# 16n.net
KiCad netlist of a schematic drawn in EAGLE
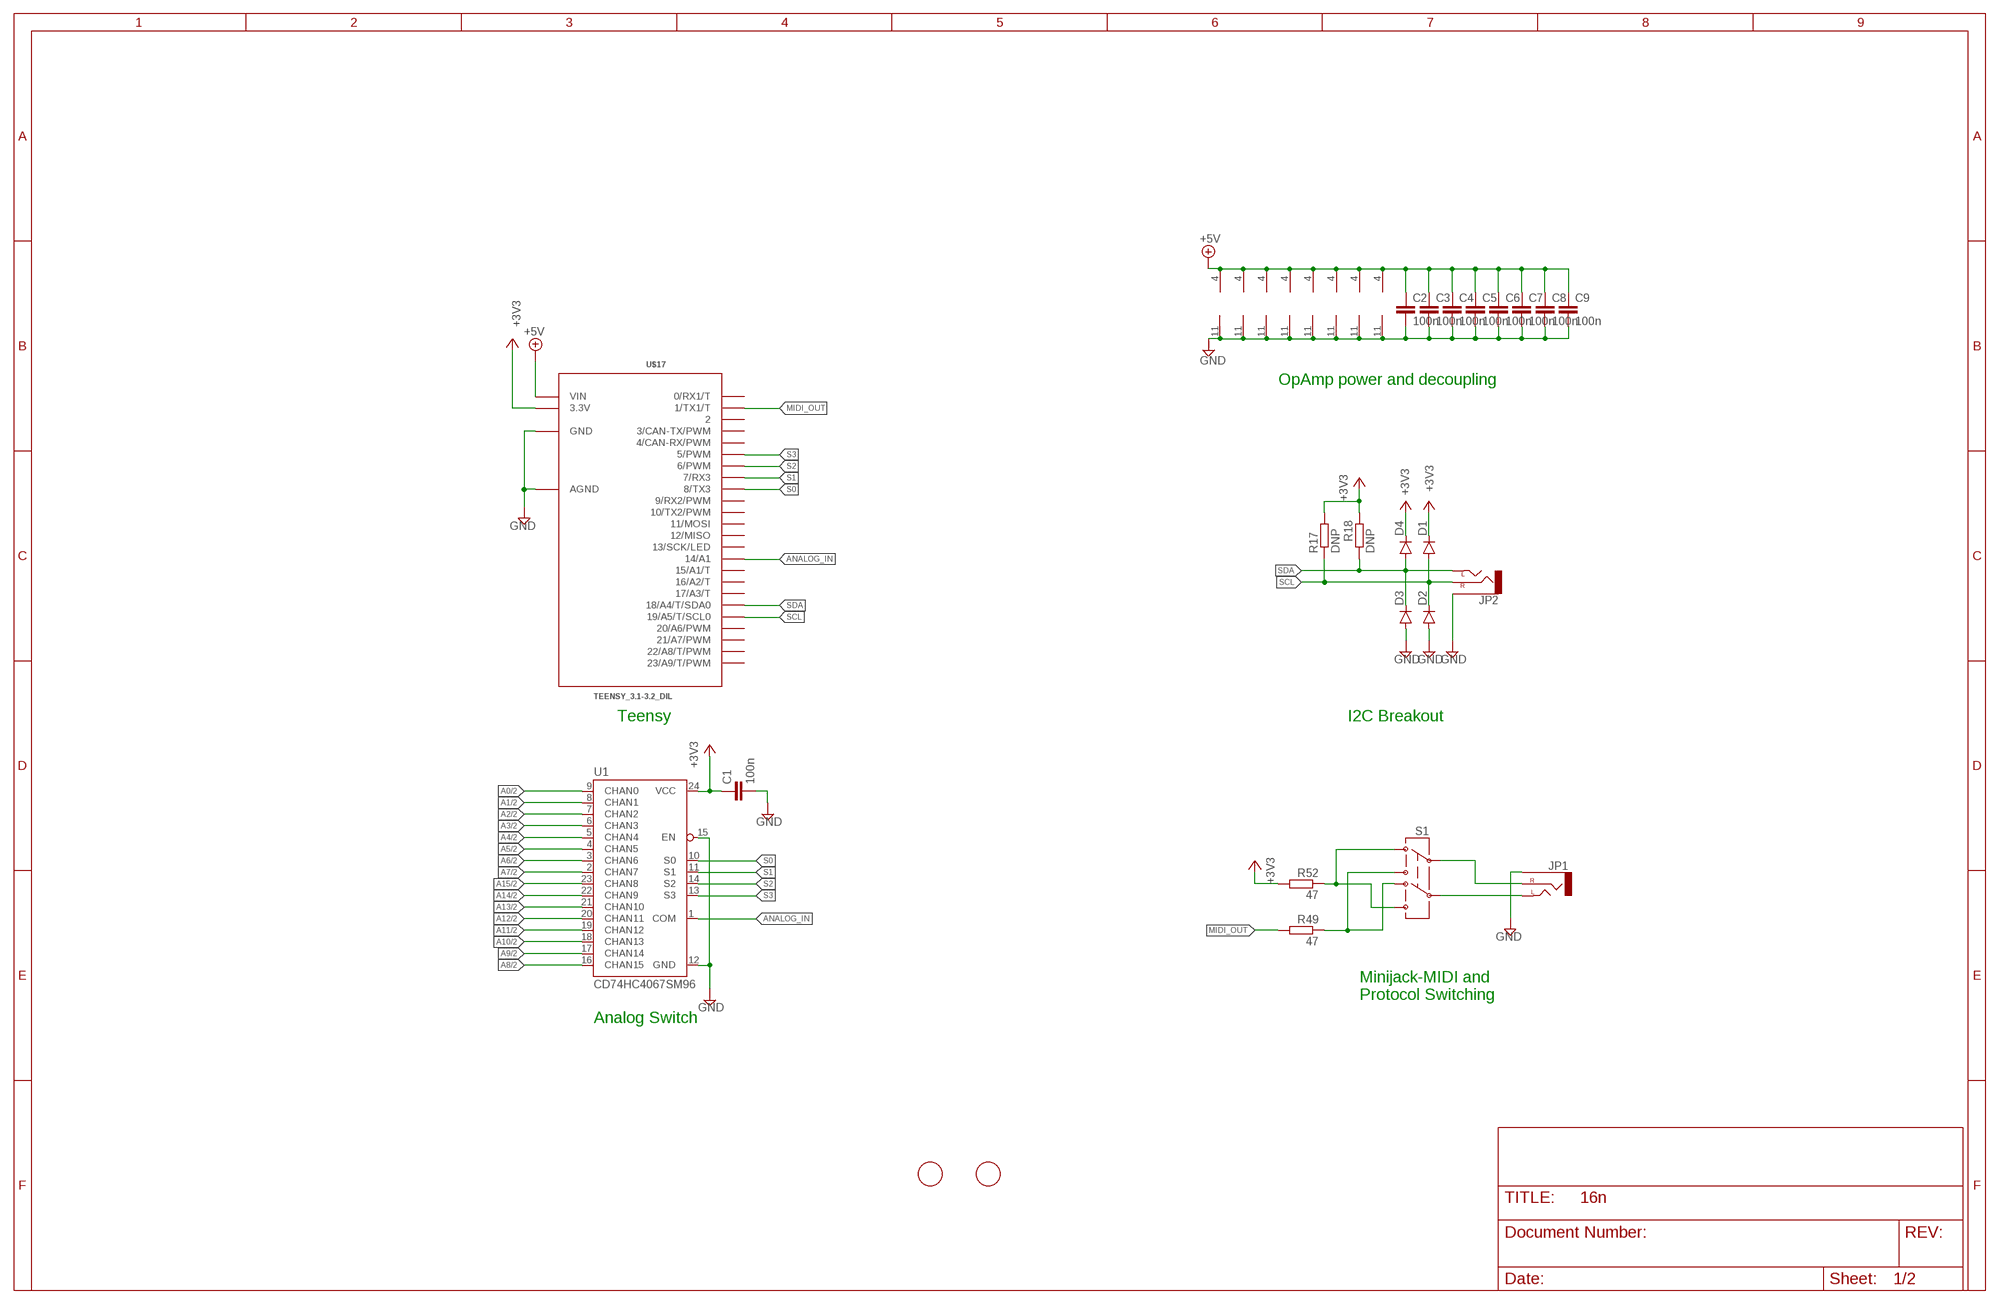
[diagram p0: schematic, sheet 1]
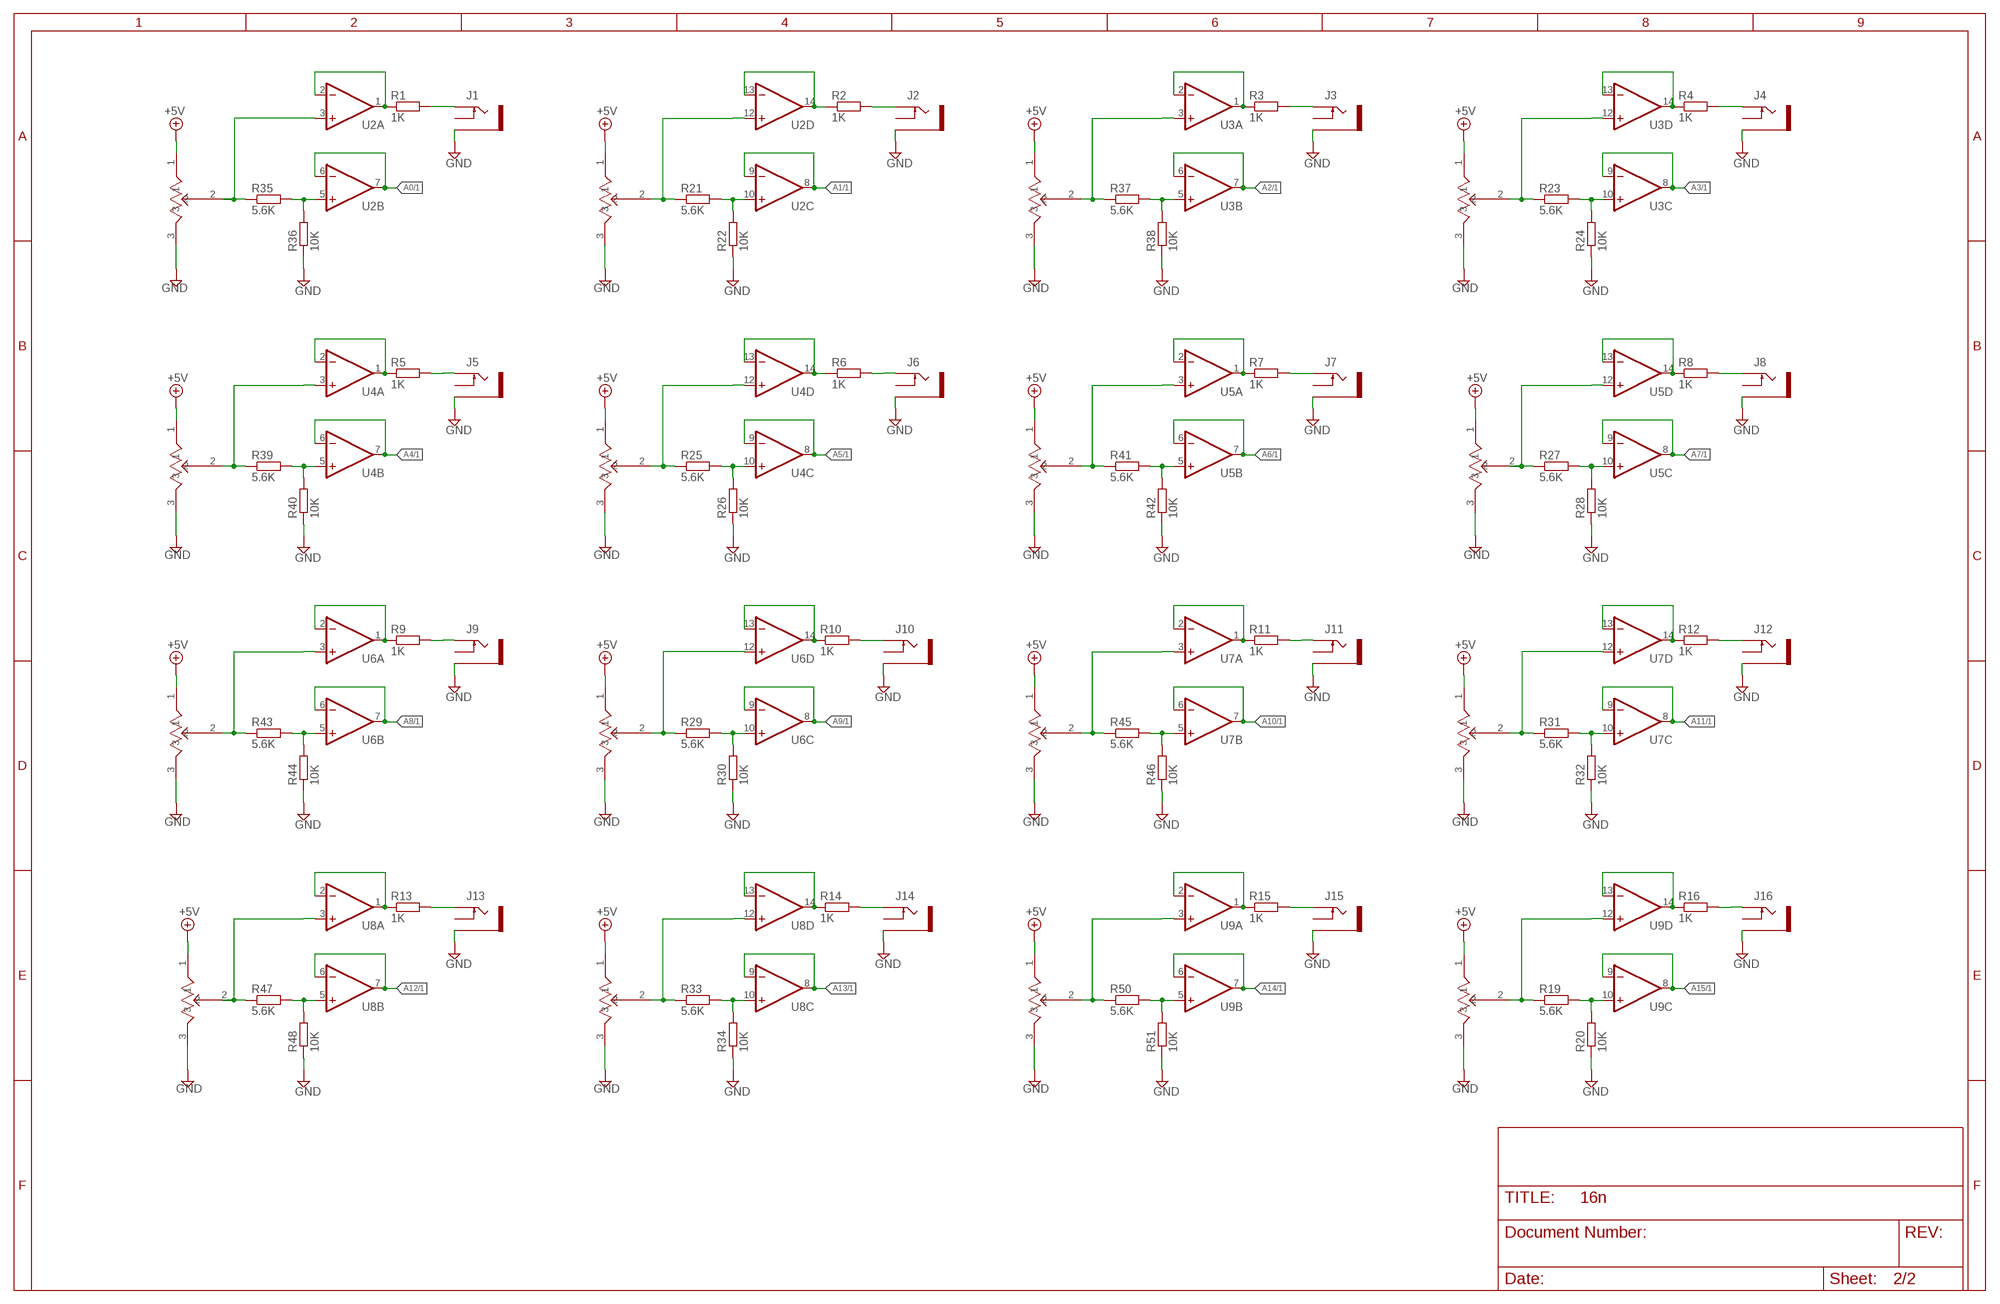
[diagram p1: schematic, sheet 2]

(export (version "E")
  (design (tool "Eeschema 10.0.6"))
  (components
    (comp (ref "C1")
      (value "100n")
      (footprint "eagle-import:C0805")
      (libsource (lib "eagle-import") (part "C-EUC0805"))
    )
    (comp (ref "C2")
      (value "100n")
      (footprint "eagle-import:C0805")
      (libsource (lib "eagle-import") (part "C-EUC0805"))
    )
    (comp (ref "C3")
      (value "100n")
      (footprint "eagle-import:C0805")
      (libsource (lib "eagle-import") (part "C-EUC0805"))
    )
    (comp (ref "C4")
      (value "100n")
      (footprint "eagle-import:C0805")
      (libsource (lib "eagle-import") (part "C-EUC0805"))
    )
    (comp (ref "C5")
      (value "100n")
      (footprint "eagle-import:C0805")
      (libsource (lib "eagle-import") (part "C-EUC0805"))
    )
    (comp (ref "C6")
      (value "100n")
      (footprint "eagle-import:C0805")
      (libsource (lib "eagle-import") (part "C-EUC0805"))
    )
    (comp (ref "C7")
      (value "100n")
      (footprint "eagle-import:C0805")
      (libsource (lib "eagle-import") (part "C-EUC0805"))
    )
    (comp (ref "C8")
      (value "100n")
      (footprint "eagle-import:C0805")
      (libsource (lib "eagle-import") (part "C-EUC0805"))
    )
    (comp (ref "C9")
      (value "100n")
      (footprint "eagle-import:C0805")
      (libsource (lib "eagle-import") (part "C-EUC0805"))
    )
    (comp (ref "D1")
      (value "DIODESOD123")
      (footprint "eagle-import:SOD-123")
      (libsource (lib "eagle-import") (part "DIODESOD123"))
    )
    (comp (ref "D2")
      (value "DIODESOD123")
      (footprint "eagle-import:SOD-123")
      (libsource (lib "eagle-import") (part "DIODESOD123"))
    )
    (comp (ref "D3")
      (value "DIODESOD123")
      (footprint "eagle-import:SOD-123")
      (libsource (lib "eagle-import") (part "DIODESOD123"))
    )
    (comp (ref "D4")
      (value "DIODESOD123")
      (footprint "eagle-import:SOD-123")
      (libsource (lib "eagle-import") (part "DIODESOD123"))
    )
    (comp (ref "FID1")
      (value "FIDUCIAL")
      (footprint "eagle-import:FIDUCIAL_1MM")
      (libsource (lib "eagle-import") (part "FIDUCIAL"))
    )
    (comp (ref "FID2")
      (value "FIDUCIAL")
      (footprint "eagle-import:FIDUCIAL_1MM")
      (libsource (lib "eagle-import") (part "FIDUCIAL"))
    )
    (comp (ref "JP1")
      (value "AUDIO-JACKPTH")
      (footprint "eagle-import:AUDIO-JACK")
      (libsource (lib "eagle-import") (part "AUDIO-JACKPTH"))
    )
    (comp (ref "JP2")
      (value "AUDIO-JACKPTH")
      (footprint "eagle-import:AUDIO-JACK")
      (libsource (lib "eagle-import") (part "AUDIO-JACKPTH"))
    )
    (comp (ref "R17")
      (value "DNP")
      (footprint "eagle-import:R0805")
      (libsource (lib "eagle-import") (part "R-EU_R0805"))
    )
    (comp (ref "R18")
      (value "DNP")
      (footprint "eagle-import:R0805")
      (libsource (lib "eagle-import") (part "R-EU_R0805"))
    )
    (comp (ref "R49")
      (value "47")
      (footprint "eagle-import:R0805")
      (libsource (lib "eagle-import") (part "R-EU_R0805"))
    )
    (comp (ref "R52")
      (value "47")
      (footprint "eagle-import:R0805")
      (libsource (lib "eagle-import") (part "R-EU_R0805"))
    )
    (comp (ref "S1")
      (value "SWITCH-DPDTEG2211")
      (footprint "eagle-import:EG2211")
      (libsource (lib "eagle-import") (part "SWITCH-DPDTEG2211"))
    )
    (comp (ref "U$17")
      (value "TEENSY_3.1-3.2_DIL")
      (footprint "eagle-import:TEENSY_3.0-3.2&LC_DIL")
      (libsource (lib "eagle-import") (part "TEENSY_3.1-3.2_DIL"))
    )
    (comp (ref "U1")
      (value "CD74HC4067SM96")
      (footprint "eagle-import:SOIC127P1030X265-24")
      (libsource (lib "eagle-import") (part "744067SO24"))
    )
    (comp (ref "U2")
      (value "MCP6004_SMD")
      (footprint "eagle-import:SO14")
      (libsource (lib "eagle-import") (part "MCP6004_SMD"))
    )
    (comp (ref "U3")
      (value "MCP6004_SMD")
      (footprint "eagle-import:SO14")
      (libsource (lib "eagle-import") (part "MCP6004_SMD"))
    )
    (comp (ref "U4")
      (value "MCP6004_SMD")
      (footprint "eagle-import:SO14")
      (libsource (lib "eagle-import") (part "MCP6004_SMD"))
    )
    (comp (ref "U5")
      (value "MCP6004_SMD")
      (footprint "eagle-import:SO14")
      (libsource (lib "eagle-import") (part "MCP6004_SMD"))
    )
    (comp (ref "U6")
      (value "MCP6004_SMD")
      (footprint "eagle-import:SO14")
      (libsource (lib "eagle-import") (part "MCP6004_SMD"))
    )
    (comp (ref "U7")
      (value "MCP6004_SMD")
      (footprint "eagle-import:SO14")
      (libsource (lib "eagle-import") (part "MCP6004_SMD"))
    )
    (comp (ref "U8")
      (value "MCP6004_SMD")
      (footprint "eagle-import:SO14")
      (libsource (lib "eagle-import") (part "MCP6004_SMD"))
    )
    (comp (ref "U9")
      (value "MCP6004")
      (footprint "eagle-import:SO14")
      (libsource (lib "eagle-import") (part "MCP6004_SMD"))
    )
    (comp (ref "J1")
      (value "PJ302M")
      (footprint "eagle-import:PJ302M")
      (libsource (lib "eagle-import") (part "PJ302M"))
    )
    (comp (ref "J2")
      (value "PJ302M")
      (footprint "eagle-import:PJ302M")
      (libsource (lib "eagle-import") (part "PJ302M"))
    )
    (comp (ref "J3")
      (value "PJ302M")
      (footprint "eagle-import:PJ302M")
      (libsource (lib "eagle-import") (part "PJ302M"))
    )
    (comp (ref "J4")
      (value "PJ302M")
      (footprint "eagle-import:PJ302M")
      (libsource (lib "eagle-import") (part "PJ302M"))
    )
    (comp (ref "J5")
      (value "PJ302M")
      (footprint "eagle-import:PJ302M")
      (libsource (lib "eagle-import") (part "PJ302M"))
    )
    (comp (ref "J6")
      (value "PJ302M")
      (footprint "eagle-import:PJ302M")
      (libsource (lib "eagle-import") (part "PJ302M"))
    )
    (comp (ref "J7")
      (value "PJ302M")
      (footprint "eagle-import:PJ302M")
      (libsource (lib "eagle-import") (part "PJ302M"))
    )
    (comp (ref "J8")
      (value "PJ302M")
      (footprint "eagle-import:PJ302M")
      (libsource (lib "eagle-import") (part "PJ302M"))
    )
    (comp (ref "J9")
      (value "PJ302M")
      (footprint "eagle-import:PJ302M")
      (libsource (lib "eagle-import") (part "PJ302M"))
    )
    (comp (ref "J10")
      (value "PJ302M")
      (footprint "eagle-import:PJ302M")
      (libsource (lib "eagle-import") (part "PJ302M"))
    )
    (comp (ref "J11")
      (value "PJ302M")
      (footprint "eagle-import:PJ302M")
      (libsource (lib "eagle-import") (part "PJ302M"))
    )
    (comp (ref "J12")
      (value "PJ302M")
      (footprint "eagle-import:PJ302M")
      (libsource (lib "eagle-import") (part "PJ302M"))
    )
    (comp (ref "J13")
      (value "PJ302M")
      (footprint "eagle-import:PJ302M")
      (libsource (lib "eagle-import") (part "PJ302M"))
    )
    (comp (ref "J14")
      (value "PJ302M")
      (footprint "eagle-import:PJ302M")
      (libsource (lib "eagle-import") (part "PJ302M"))
    )
    (comp (ref "J15")
      (value "PJ302M")
      (footprint "eagle-import:PJ302M")
      (libsource (lib "eagle-import") (part "PJ302M"))
    )
    (comp (ref "J16")
      (value "PJ302M")
      (footprint "eagle-import:PJ302M")
      (libsource (lib "eagle-import") (part "PJ302M"))
    )
    (comp (ref "R1")
      (value "1K")
      (footprint "eagle-import:R0805")
      (libsource (lib "eagle-import") (part "R-EU_R0805"))
    )
    (comp (ref "R2")
      (value "1K")
      (footprint "eagle-import:R0805")
      (libsource (lib "eagle-import") (part "R-EU_R0805"))
    )
    (comp (ref "R3")
      (value "1K")
      (footprint "eagle-import:R0805")
      (libsource (lib "eagle-import") (part "R-EU_R0805"))
    )
    (comp (ref "R4")
      (value "1K")
      (footprint "eagle-import:R0805")
      (libsource (lib "eagle-import") (part "R-EU_R0805"))
    )
    (comp (ref "R5")
      (value "1K")
      (footprint "eagle-import:R0805")
      (libsource (lib "eagle-import") (part "R-EU_R0805"))
    )
    (comp (ref "R6")
      (value "1K")
      (footprint "eagle-import:R0805")
      (libsource (lib "eagle-import") (part "R-EU_R0805"))
    )
    (comp (ref "R7")
      (value "1K")
      (footprint "eagle-import:R0805")
      (libsource (lib "eagle-import") (part "R-EU_R0805"))
    )
    (comp (ref "R8")
      (value "1K")
      (footprint "eagle-import:R0805")
      (libsource (lib "eagle-import") (part "R-EU_R0805"))
    )
    (comp (ref "R9")
      (value "1K")
      (footprint "eagle-import:R0805")
      (libsource (lib "eagle-import") (part "R-EU_R0805"))
    )
    (comp (ref "R10")
      (value "1K")
      (footprint "eagle-import:R0805")
      (libsource (lib "eagle-import") (part "R-EU_R0805"))
    )
    (comp (ref "R11")
      (value "1K")
      (footprint "eagle-import:R0805")
      (libsource (lib "eagle-import") (part "R-EU_R0805"))
    )
    (comp (ref "R12")
      (value "1K")
      (footprint "eagle-import:R0805")
      (libsource (lib "eagle-import") (part "R-EU_R0805"))
    )
    (comp (ref "R13")
      (value "1K")
      (footprint "eagle-import:R0805")
      (libsource (lib "eagle-import") (part "R-EU_R0805"))
    )
    (comp (ref "R14")
      (value "1K")
      (footprint "eagle-import:R0805")
      (libsource (lib "eagle-import") (part "R-EU_R0805"))
    )
    (comp (ref "R15")
      (value "1K")
      (footprint "eagle-import:R0805")
      (libsource (lib "eagle-import") (part "R-EU_R0805"))
    )
    (comp (ref "R16")
      (value "1K")
      (footprint "eagle-import:R0805")
      (libsource (lib "eagle-import") (part "R-EU_R0805"))
    )
    (comp (ref "R19")
      (value "5.6K")
      (footprint "eagle-import:R0805")
      (libsource (lib "eagle-import") (part "R-EU_R0805"))
    )
    (comp (ref "R20")
      (value "10K")
      (footprint "eagle-import:R0805")
      (libsource (lib "eagle-import") (part "R-EU_R0805"))
    )
    (comp (ref "R21")
      (value "5.6K")
      (footprint "eagle-import:R0805")
      (libsource (lib "eagle-import") (part "R-EU_R0805"))
    )
    (comp (ref "R22")
      (value "10K")
      (footprint "eagle-import:R0805")
      (libsource (lib "eagle-import") (part "R-EU_R0805"))
    )
    (comp (ref "R23")
      (value "5.6K")
      (footprint "eagle-import:R0805")
      (libsource (lib "eagle-import") (part "R-EU_R0805"))
    )
    (comp (ref "R24")
      (value "10K")
      (footprint "eagle-import:R0805")
      (libsource (lib "eagle-import") (part "R-EU_R0805"))
    )
    (comp (ref "R25")
      (value "5.6K")
      (footprint "eagle-import:R0805")
      (libsource (lib "eagle-import") (part "R-EU_R0805"))
    )
    (comp (ref "R26")
      (value "10K")
      (footprint "eagle-import:R0805")
      (libsource (lib "eagle-import") (part "R-EU_R0805"))
    )
    (comp (ref "R27")
      (value "5.6K")
      (footprint "eagle-import:R0805")
      (libsource (lib "eagle-import") (part "R-EU_R0805"))
    )
    (comp (ref "R28")
      (value "10K")
      (footprint "eagle-import:R0805")
      (libsource (lib "eagle-import") (part "R-EU_R0805"))
    )
    (comp (ref "R29")
      (value "5.6K")
      (footprint "eagle-import:R0805")
      (libsource (lib "eagle-import") (part "R-EU_R0805"))
    )
    (comp (ref "R30")
      (value "10K")
      (footprint "eagle-import:R0805")
      (libsource (lib "eagle-import") (part "R-EU_R0805"))
    )
    (comp (ref "R31")
      (value "5.6K")
      (footprint "eagle-import:R0805")
      (libsource (lib "eagle-import") (part "R-EU_R0805"))
    )
    (comp (ref "R32")
      (value "10K")
      (footprint "eagle-import:R0805")
      (libsource (lib "eagle-import") (part "R-EU_R0805"))
    )
    (comp (ref "R33")
      (value "5.6K")
      (footprint "eagle-import:R0805")
      (libsource (lib "eagle-import") (part "R-EU_R0805"))
    )
    (comp (ref "R34")
      (value "10K")
      (footprint "eagle-import:R0805")
      (libsource (lib "eagle-import") (part "R-EU_R0805"))
    )
    (comp (ref "R35")
      (value "5.6K")
      (footprint "eagle-import:R0805")
      (libsource (lib "eagle-import") (part "R-EU_R0805"))
    )
    (comp (ref "R36")
      (value "10K")
      (footprint "eagle-import:R0805")
      (libsource (lib "eagle-import") (part "R-EU_R0805"))
    )
    (comp (ref "R37")
      (value "5.6K")
      (footprint "eagle-import:R0805")
      (libsource (lib "eagle-import") (part "R-EU_R0805"))
    )
    (comp (ref "R38")
      (value "10K")
      (footprint "eagle-import:R0805")
      (libsource (lib "eagle-import") (part "R-EU_R0805"))
    )
    (comp (ref "R39")
      (value "5.6K")
      (footprint "eagle-import:R0805")
      (libsource (lib "eagle-import") (part "R-EU_R0805"))
    )
    (comp (ref "R40")
      (value "10K")
      (footprint "eagle-import:R0805")
      (libsource (lib "eagle-import") (part "R-EU_R0805"))
    )
    (comp (ref "R41")
      (value "5.6K")
      (footprint "eagle-import:R0805")
      (libsource (lib "eagle-import") (part "R-EU_R0805"))
    )
    (comp (ref "R42")
      (value "10K")
      (footprint "eagle-import:R0805")
      (libsource (lib "eagle-import") (part "R-EU_R0805"))
    )
    (comp (ref "R43")
      (value "5.6K")
      (footprint "eagle-import:R0805")
      (libsource (lib "eagle-import") (part "R-EU_R0805"))
    )
    (comp (ref "R44")
      (value "10K")
      (footprint "eagle-import:R0805")
      (libsource (lib "eagle-import") (part "R-EU_R0805"))
    )
    (comp (ref "R45")
      (value "5.6K")
      (footprint "eagle-import:R0805")
      (libsource (lib "eagle-import") (part "R-EU_R0805"))
    )
    (comp (ref "R46")
      (value "10K")
      (footprint "eagle-import:R0805")
      (libsource (lib "eagle-import") (part "R-EU_R0805"))
    )
    (comp (ref "R47")
      (value "5.6K")
      (footprint "eagle-import:R0805")
      (libsource (lib "eagle-import") (part "R-EU_R0805"))
    )
    (comp (ref "R48")
      (value "10K")
      (footprint "eagle-import:R0805")
      (libsource (lib "eagle-import") (part "R-EU_R0805"))
    )
    (comp (ref "R50")
      (value "5.6K")
      (footprint "eagle-import:R0805")
      (libsource (lib "eagle-import") (part "R-EU_R0805"))
    )
    (comp (ref "R51")
      (value "10K")
      (footprint "eagle-import:R0805")
      (libsource (lib "eagle-import") (part "R-EU_R0805"))
    )
    (comp (ref "U$1")
      (value "SLIDEPOT-ALPS-60MM")
      (footprint "eagle-import:RS6011SP600")
      (libsource (lib "eagle-import") (part "SLIDEPOT-ALPS-60MM"))
    )
    (comp (ref "U$2")
      (value "SLIDEPOT-ALPS-60MM")
      (footprint "eagle-import:RS6011SP600")
      (libsource (lib "eagle-import") (part "SLIDEPOT-ALPS-60MM"))
    )
    (comp (ref "U$3")
      (value "SLIDEPOT-ALPS-60MM")
      (footprint "eagle-import:RS6011SP600")
      (libsource (lib "eagle-import") (part "SLIDEPOT-ALPS-60MM"))
    )
    (comp (ref "U$4")
      (value "SLIDEPOT-ALPS-60MM")
      (footprint "eagle-import:RS6011SP600")
      (libsource (lib "eagle-import") (part "SLIDEPOT-ALPS-60MM"))
    )
    (comp (ref "U$5")
      (value "SLIDEPOT-ALPS-60MM")
      (footprint "eagle-import:RS6011SP600")
      (libsource (lib "eagle-import") (part "SLIDEPOT-ALPS-60MM"))
    )
    (comp (ref "U$6")
      (value "SLIDEPOT-ALPS-60MM")
      (footprint "eagle-import:RS6011SP600")
      (libsource (lib "eagle-import") (part "SLIDEPOT-ALPS-60MM"))
    )
    (comp (ref "U$7")
      (value "SLIDEPOT-ALPS-60MM")
      (footprint "eagle-import:RS6011SP600")
      (libsource (lib "eagle-import") (part "SLIDEPOT-ALPS-60MM"))
    )
    (comp (ref "U$8")
      (value "SLIDEPOT-ALPS-60MM")
      (footprint "eagle-import:RS6011SP600")
      (libsource (lib "eagle-import") (part "SLIDEPOT-ALPS-60MM"))
    )
    (comp (ref "U$9")
      (value "SLIDEPOT-ALPS-60MM")
      (footprint "eagle-import:RS6011SP600")
      (libsource (lib "eagle-import") (part "SLIDEPOT-ALPS-60MM"))
    )
    (comp (ref "U$10")
      (value "SLIDEPOT-ALPS-60MM")
      (footprint "eagle-import:RS6011SP600")
      (fields (field (name "SPICEPREFIX") "U"))
      (libsource (lib "eagle-import") (part "SLIDEPOT-ALPS-60MM"))
    )
    (comp (ref "U$11")
      (value "SLIDEPOT-ALPS-60MM")
      (footprint "eagle-import:RS6011SP600")
      (libsource (lib "eagle-import") (part "SLIDEPOT-ALPS-60MM"))
    )
    (comp (ref "U$12")
      (value "SLIDEPOT-ALPS-60MM")
      (footprint "eagle-import:RS6011SP600")
      (libsource (lib "eagle-import") (part "SLIDEPOT-ALPS-60MM"))
    )
    (comp (ref "U$13")
      (value "SLIDEPOT-ALPS-60MM")
      (footprint "eagle-import:RS6011SP600")
      (libsource (lib "eagle-import") (part "SLIDEPOT-ALPS-60MM"))
    )
    (comp (ref "U$14")
      (value "SLIDEPOT-ALPS-60MM")
      (footprint "eagle-import:RS6011SP600")
      (libsource (lib "eagle-import") (part "SLIDEPOT-ALPS-60MM"))
    )
    (comp (ref "U$15")
      (value "SLIDEPOT-ALPS-60MM")
      (footprint "eagle-import:RS6011SP600")
      (libsource (lib "eagle-import") (part "SLIDEPOT-ALPS-60MM"))
    )
    (comp (ref "U$16")
      (value "SLIDEPOT-ALPS-60MM")
      (footprint "eagle-import:RS6011SP600")
      (libsource (lib "eagle-import") (part "SLIDEPOT-ALPS-60MM"))
    )
  )
  (nets
    (net (code "1") (name "+3V3") (class "Default")
      (node (ref "C1") (pin "1") (pinfunction "1_1") (pintype "passive"))
      (node (ref "D1") (pin "C") (pinfunction "C_C") (pintype "passive"))
      (node (ref "D4") (pin "C") (pinfunction "C_C") (pintype "passive"))
      (node (ref "R17") (pin "2") (pinfunction "2_2") (pintype "passive"))
      (node (ref "R18") (pin "2") (pinfunction "2_2") (pintype "passive"))
      (node (ref "R52") (pin "2") (pinfunction "2_2") (pintype "passive"))
      (node (ref "U$17") (pin "3.3V") (pinfunction "3.3V_3.3V") (pintype "power_in"))
      (node (ref "U1") (pin "24") (pinfunction "VCC_24") (pintype "bidirectional"))
    )
    (net (code "2") (name "+5V") (class "Default")
      (node (ref "C2") (pin "1") (pinfunction "1_1") (pintype "passive"))
      (node (ref "C3") (pin "1") (pinfunction "1_1") (pintype "passive"))
      (node (ref "C4") (pin "1") (pinfunction "1_1") (pintype "passive"))
      (node (ref "C5") (pin "1") (pinfunction "1_1") (pintype "passive"))
      (node (ref "C6") (pin "1") (pinfunction "1_1") (pintype "passive"))
      (node (ref "C7") (pin "1") (pinfunction "1_1") (pintype "passive"))
      (node (ref "C8") (pin "1") (pinfunction "1_1") (pintype "passive"))
      (node (ref "C9") (pin "1") (pinfunction "1_1") (pintype "passive"))
      (node (ref "U$1") (pin "1") (pinfunction "1_1") (pintype "bidirectional"))
      (node (ref "U$10") (pin "1") (pinfunction "1_1") (pintype "bidirectional"))
      (node (ref "U$11") (pin "1") (pinfunction "1_1") (pintype "bidirectional"))
      (node (ref "U$12") (pin "1") (pinfunction "1_1") (pintype "bidirectional"))
      (node (ref "U$13") (pin "1") (pinfunction "1_1") (pintype "bidirectional"))
      (node (ref "U$14") (pin "1") (pinfunction "1_1") (pintype "bidirectional"))
      (node (ref "U$15") (pin "1") (pinfunction "1_1") (pintype "bidirectional"))
      (node (ref "U$16") (pin "1") (pinfunction "1_1") (pintype "bidirectional"))
      (node (ref "U$17") (pin "VIN") (pinfunction "VIN_VIN") (pintype "power_in"))
      (node (ref "U$2") (pin "1") (pinfunction "1_1") (pintype "bidirectional"))
      (node (ref "U$3") (pin "1") (pinfunction "1_1") (pintype "bidirectional"))
      (node (ref "U$4") (pin "1") (pinfunction "1_1") (pintype "bidirectional"))
      (node (ref "U$5") (pin "1") (pinfunction "1_1") (pintype "bidirectional"))
      (node (ref "U$6") (pin "1") (pinfunction "1_1") (pintype "bidirectional"))
      (node (ref "U$7") (pin "1") (pinfunction "1_1") (pintype "bidirectional"))
      (node (ref "U$8") (pin "1") (pinfunction "1_1") (pintype "bidirectional"))
      (node (ref "U$9") (pin "1") (pinfunction "1_1") (pintype "bidirectional"))
      (node (ref "U2") (pin "4") (pinfunction "V+_4") (pintype "power_in"))
      (node (ref "U3") (pin "4") (pinfunction "V+_4") (pintype "power_in"))
      (node (ref "U4") (pin "4") (pinfunction "V+_4") (pintype "power_in"))
      (node (ref "U5") (pin "4") (pinfunction "V+_4") (pintype "power_in"))
      (node (ref "U6") (pin "4") (pinfunction "V+_4") (pintype "power_in"))
      (node (ref "U7") (pin "4") (pinfunction "V+_4") (pintype "power_in"))
      (node (ref "U8") (pin "4") (pinfunction "V+_4") (pintype "power_in"))
      (node (ref "U9") (pin "4") (pinfunction "V+_4") (pintype "power_in"))
    )
    (net (code "3") (name "A0") (class "Default")
      (node (ref "U1") (pin "9") (pinfunction "CHAN0_9") (pintype "bidirectional"))
      (node (ref "U2") (pin "6") (pinfunction "-IN_6") (pintype "input"))
      (node (ref "U2") (pin "7") (pinfunction "OUT_7") (pintype "output"))
    )
    (net (code "4") (name "A1") (class "Default")
      (node (ref "U1") (pin "8") (pinfunction "CHAN1_8") (pintype "bidirectional"))
      (node (ref "U2") (pin "8") (pinfunction "OUT_8") (pintype "output"))
      (node (ref "U2") (pin "9") (pinfunction "-IN_9") (pintype "input"))
    )
    (net (code "5") (name "A2") (class "Default")
      (node (ref "U1") (pin "7") (pinfunction "CHAN2_7") (pintype "bidirectional"))
      (node (ref "U3") (pin "6") (pinfunction "-IN_6") (pintype "input"))
      (node (ref "U3") (pin "7") (pinfunction "OUT_7") (pintype "output"))
    )
    (net (code "6") (name "A3") (class "Default")
      (node (ref "U1") (pin "6") (pinfunction "CHAN3_6") (pintype "bidirectional"))
      (node (ref "U3") (pin "8") (pinfunction "OUT_8") (pintype "output"))
      (node (ref "U3") (pin "9") (pinfunction "-IN_9") (pintype "input"))
    )
    (net (code "7") (name "A4") (class "Default")
      (node (ref "U1") (pin "5") (pinfunction "CHAN4_5") (pintype "bidirectional"))
      (node (ref "U4") (pin "6") (pinfunction "-IN_6") (pintype "input"))
      (node (ref "U4") (pin "7") (pinfunction "OUT_7") (pintype "output"))
    )
    (net (code "8") (name "A5") (class "Default")
      (node (ref "U1") (pin "4") (pinfunction "CHAN5_4") (pintype "bidirectional"))
      (node (ref "U4") (pin "8") (pinfunction "OUT_8") (pintype "output"))
      (node (ref "U4") (pin "9") (pinfunction "-IN_9") (pintype "input"))
    )
    (net (code "9") (name "A6") (class "Default")
      (node (ref "U1") (pin "3") (pinfunction "CHAN6_3") (pintype "bidirectional"))
      (node (ref "U5") (pin "6") (pinfunction "-IN_6") (pintype "input"))
      (node (ref "U5") (pin "7") (pinfunction "OUT_7") (pintype "output"))
    )
    (net (code "10") (name "A7") (class "Default")
      (node (ref "U1") (pin "2") (pinfunction "CHAN7_2") (pintype "bidirectional"))
      (node (ref "U5") (pin "8") (pinfunction "OUT_8") (pintype "output"))
      (node (ref "U5") (pin "9") (pinfunction "-IN_9") (pintype "input"))
    )
    (net (code "11") (name "A8") (class "Default")
      (node (ref "U1") (pin "16") (pinfunction "CHAN15_16") (pintype "bidirectional"))
      (node (ref "U6") (pin "6") (pinfunction "-IN_6") (pintype "input"))
      (node (ref "U6") (pin "7") (pinfunction "OUT_7") (pintype "output"))
    )
    (net (code "12") (name "A9") (class "Default")
      (node (ref "U1") (pin "17") (pinfunction "CHAN14_17") (pintype "bidirectional"))
      (node (ref "U6") (pin "8") (pinfunction "OUT_8") (pintype "output"))
      (node (ref "U6") (pin "9") (pinfunction "-IN_9") (pintype "input"))
    )
    (net (code "13") (name "A10") (class "Default")
      (node (ref "U1") (pin "18") (pinfunction "CHAN13_18") (pintype "bidirectional"))
      (node (ref "U7") (pin "6") (pinfunction "-IN_6") (pintype "input"))
      (node (ref "U7") (pin "7") (pinfunction "OUT_7") (pintype "output"))
    )
    (net (code "14") (name "A11") (class "Default")
      (node (ref "U1") (pin "19") (pinfunction "CHAN12_19") (pintype "bidirectional"))
      (node (ref "U7") (pin "8") (pinfunction "OUT_8") (pintype "output"))
      (node (ref "U7") (pin "9") (pinfunction "-IN_9") (pintype "input"))
    )
    (net (code "15") (name "A12") (class "Default")
      (node (ref "U1") (pin "20") (pinfunction "CHAN11_20") (pintype "bidirectional"))
      (node (ref "U8") (pin "6") (pinfunction "-IN_6") (pintype "input"))
      (node (ref "U8") (pin "7") (pinfunction "OUT_7") (pintype "output"))
    )
    (net (code "16") (name "A13") (class "Default")
      (node (ref "U1") (pin "21") (pinfunction "CHAN10_21") (pintype "bidirectional"))
      (node (ref "U8") (pin "8") (pinfunction "OUT_8") (pintype "output"))
      (node (ref "U8") (pin "9") (pinfunction "-IN_9") (pintype "input"))
    )
    (net (code "17") (name "A14") (class "Default")
      (node (ref "U1") (pin "22") (pinfunction "CHAN9_22") (pintype "bidirectional"))
      (node (ref "U9") (pin "6") (pinfunction "-IN_6") (pintype "input"))
      (node (ref "U9") (pin "7") (pinfunction "OUT_7") (pintype "output"))
    )
    (net (code "18") (name "A15") (class "Default")
      (node (ref "U1") (pin "23") (pinfunction "CHAN8_23") (pintype "bidirectional"))
      (node (ref "U9") (pin "8") (pinfunction "OUT_8") (pintype "output"))
      (node (ref "U9") (pin "9") (pinfunction "-IN_9") (pintype "input"))
    )
    (net (code "19") (name "ANALOG_IN") (class "Default")
      (node (ref "U$17") (pin "14/A0") (pinfunction "14/A1_14/A0") (pintype "bidirectional"))
      (node (ref "U1") (pin "1") (pinfunction "COM_1") (pintype "bidirectional"))
    )
    (net (code "20") (name "GND") (class "Default")
      (node (ref "C1") (pin "2") (pinfunction "2_2") (pintype "passive"))
      (node (ref "C2") (pin "2") (pinfunction "2_2") (pintype "passive"))
      (node (ref "C3") (pin "2") (pinfunction "2_2") (pintype "passive"))
      (node (ref "C4") (pin "2") (pinfunction "2_2") (pintype "passive"))
      (node (ref "C5") (pin "2") (pinfunction "2_2") (pintype "passive"))
      (node (ref "C6") (pin "2") (pinfunction "2_2") (pintype "passive"))
      (node (ref "C7") (pin "2") (pinfunction "2_2") (pintype "passive"))
      (node (ref "C8") (pin "2") (pinfunction "2_2") (pintype "passive"))
      (node (ref "C9") (pin "2") (pinfunction "2_2") (pintype "passive"))
      (node (ref "D2") (pin "A") (pinfunction "A_A") (pintype "passive"))
      (node (ref "D3") (pin "A") (pinfunction "A_A") (pintype "passive"))
      (node (ref "J1") (pin "GND") (pinfunction "SLEEVE_GND") (pintype "passive"))
      (node (ref "J10") (pin "GND") (pinfunction "SLEEVE_GND") (pintype "passive"))
      (node (ref "J11") (pin "GND") (pinfunction "SLEEVE_GND") (pintype "passive"))
      (node (ref "J12") (pin "GND") (pinfunction "SLEEVE_GND") (pintype "passive"))
      (node (ref "J13") (pin "GND") (pinfunction "SLEEVE_GND") (pintype "passive"))
      (node (ref "J14") (pin "GND") (pinfunction "SLEEVE_GND") (pintype "passive"))
      (node (ref "J15") (pin "GND") (pinfunction "SLEEVE_GND") (pintype "passive"))
      (node (ref "J16") (pin "GND") (pinfunction "SLEEVE_GND") (pintype "passive"))
      (node (ref "J2") (pin "GND") (pinfunction "SLEEVE_GND") (pintype "passive"))
      (node (ref "J3") (pin "GND") (pinfunction "SLEEVE_GND") (pintype "passive"))
      (node (ref "J4") (pin "GND") (pinfunction "SLEEVE_GND") (pintype "passive"))
      (node (ref "J5") (pin "GND") (pinfunction "SLEEVE_GND") (pintype "passive"))
      (node (ref "J6") (pin "GND") (pinfunction "SLEEVE_GND") (pintype "passive"))
      (node (ref "J7") (pin "GND") (pinfunction "SLEEVE_GND") (pintype "passive"))
      (node (ref "J8") (pin "GND") (pinfunction "SLEEVE_GND") (pintype "passive"))
      (node (ref "J9") (pin "GND") (pinfunction "SLEEVE_GND") (pintype "passive"))
      (node (ref "JP1") (pin "SLEEVE") (pinfunction "SLEEVE_SLEEVE") (pintype "bidirectional"))
      (node (ref "JP2") (pin "SLEEVE") (pinfunction "SLEEVE_SLEEVE") (pintype "bidirectional"))
      (node (ref "R20") (pin "1") (pinfunction "1_1") (pintype "passive"))
      (node (ref "R22") (pin "1") (pinfunction "1_1") (pintype "passive"))
      (node (ref "R24") (pin "1") (pinfunction "1_1") (pintype "passive"))
      (node (ref "R26") (pin "1") (pinfunction "1_1") (pintype "passive"))
      (node (ref "R28") (pin "1") (pinfunction "1_1") (pintype "passive"))
      (node (ref "R30") (pin "1") (pinfunction "1_1") (pintype "passive"))
      (node (ref "R32") (pin "1") (pinfunction "1_1") (pintype "passive"))
      (node (ref "R34") (pin "1") (pinfunction "1_1") (pintype "passive"))
      (node (ref "R36") (pin "1") (pinfunction "1_1") (pintype "passive"))
      (node (ref "R38") (pin "1") (pinfunction "1_1") (pintype "passive"))
      (node (ref "R40") (pin "1") (pinfunction "1_1") (pintype "passive"))
      (node (ref "R42") (pin "1") (pinfunction "1_1") (pintype "passive"))
      (node (ref "R44") (pin "1") (pinfunction "1_1") (pintype "passive"))
      (node (ref "R46") (pin "1") (pinfunction "1_1") (pintype "passive"))
      (node (ref "R48") (pin "1") (pinfunction "1_1") (pintype "passive"))
      (node (ref "R51") (pin "1") (pinfunction "1_1") (pintype "passive"))
      (node (ref "U$1") (pin "3") (pinfunction "3_3") (pintype "bidirectional"))
      (node (ref "U$10") (pin "3") (pinfunction "3_3") (pintype "bidirectional"))
      (node (ref "U$11") (pin "3") (pinfunction "3_3") (pintype "bidirectional"))
      (node (ref "U$12") (pin "3") (pinfunction "3_3") (pintype "bidirectional"))
      (node (ref "U$13") (pin "3") (pinfunction "3_3") (pintype "bidirectional"))
      (node (ref "U$14") (pin "3") (pinfunction "3_3") (pintype "bidirectional"))
      (node (ref "U$15") (pin "3") (pinfunction "3_3") (pintype "bidirectional"))
      (node (ref "U$16") (pin "3") (pinfunction "3_3") (pintype "bidirectional"))
      (node (ref "U$17") (pin "AGND") (pinfunction "AGND_AGND") (pintype "power_in"))
      (node (ref "U$17") (pin "GND") (pinfunction "GND_GND") (pintype "power_in"))
      (node (ref "U$2") (pin "3") (pinfunction "3_3") (pintype "bidirectional"))
      (node (ref "U$3") (pin "3") (pinfunction "3_3") (pintype "bidirectional"))
      (node (ref "U$4") (pin "3") (pinfunction "3_3") (pintype "bidirectional"))
      (node (ref "U$5") (pin "3") (pinfunction "3_3") (pintype "bidirectional"))
      (node (ref "U$6") (pin "3") (pinfunction "3_3") (pintype "bidirectional"))
      (node (ref "U$7") (pin "3") (pinfunction "3_3") (pintype "bidirectional"))
      (node (ref "U$8") (pin "3") (pinfunction "3_3") (pintype "bidirectional"))
      (node (ref "U$9") (pin "3") (pinfunction "3_3") (pintype "bidirectional"))
      (node (ref "U1") (pin "12") (pinfunction "GND_12") (pintype "bidirectional"))
      (node (ref "U1") (pin "15") (pinfunction "EN_15") (pintype "input"))
      (node (ref "U2") (pin "11") (pinfunction "V-_11") (pintype "power_in"))
      (node (ref "U3") (pin "11") (pinfunction "V-_11") (pintype "power_in"))
      (node (ref "U4") (pin "11") (pinfunction "V-_11") (pintype "power_in"))
      (node (ref "U5") (pin "11") (pinfunction "V-_11") (pintype "power_in"))
      (node (ref "U6") (pin "11") (pinfunction "V-_11") (pintype "power_in"))
      (node (ref "U7") (pin "11") (pinfunction "V-_11") (pintype "power_in"))
      (node (ref "U8") (pin "11") (pinfunction "V-_11") (pintype "power_in"))
      (node (ref "U9") (pin "11") (pinfunction "V-_11") (pintype "power_in"))
    )
    (net (code "21") (name "MIDI_OUT") (class "Default")
      (node (ref "R49") (pin "2") (pinfunction "2_2") (pintype "passive"))
      (node (ref "U$17") (pin "1") (pinfunction "1/TX1/T_1") (pintype "bidirectional"))
    )
    (net (code "22") (name "Net-(J1-PadTIP)") (class "Default")
      (node (ref "J1") (pin "TIP") (pinfunction "TIP_TIP") (pintype "passive"))
      (node (ref "R1") (pin "2") (pinfunction "2_2") (pintype "passive"))
    )
    (net (code "23") (name "Net-(J2-PadTIP)") (class "Default")
      (node (ref "J2") (pin "TIP") (pinfunction "TIP_TIP") (pintype "passive"))
      (node (ref "R2") (pin "2") (pinfunction "2_2") (pintype "passive"))
    )
    (net (code "24") (name "Net-(J3-PadTIP)") (class "Default")
      (node (ref "J3") (pin "TIP") (pinfunction "TIP_TIP") (pintype "passive"))
      (node (ref "R3") (pin "2") (pinfunction "2_2") (pintype "passive"))
    )
    (net (code "25") (name "Net-(J4-PadTIP)") (class "Default")
      (node (ref "J4") (pin "TIP") (pinfunction "TIP_TIP") (pintype "passive"))
      (node (ref "R4") (pin "2") (pinfunction "2_2") (pintype "passive"))
    )
    (net (code "26") (name "Net-(J5-PadTIP)") (class "Default")
      (node (ref "J5") (pin "TIP") (pinfunction "TIP_TIP") (pintype "passive"))
      (node (ref "R5") (pin "2") (pinfunction "2_2") (pintype "passive"))
    )
    (net (code "27") (name "Net-(J6-PadTIP)") (class "Default")
      (node (ref "J6") (pin "TIP") (pinfunction "TIP_TIP") (pintype "passive"))
      (node (ref "R6") (pin "2") (pinfunction "2_2") (pintype "passive"))
    )
    (net (code "28") (name "Net-(J7-PadTIP)") (class "Default")
      (node (ref "J7") (pin "TIP") (pinfunction "TIP_TIP") (pintype "passive"))
      (node (ref "R7") (pin "2") (pinfunction "2_2") (pintype "passive"))
    )
    (net (code "29") (name "Net-(J8-PadTIP)") (class "Default")
      (node (ref "J8") (pin "TIP") (pinfunction "TIP_TIP") (pintype "passive"))
      (node (ref "R8") (pin "2") (pinfunction "2_2") (pintype "passive"))
    )
    (net (code "30") (name "Net-(J9-PadTIP)") (class "Default")
      (node (ref "J9") (pin "TIP") (pinfunction "TIP_TIP") (pintype "passive"))
      (node (ref "R9") (pin "2") (pinfunction "2_2") (pintype "passive"))
    )
    (net (code "31") (name "Net-(J10-PadTIP)") (class "Default")
      (node (ref "J10") (pin "TIP") (pinfunction "TIP_TIP") (pintype "passive"))
      (node (ref "R10") (pin "2") (pinfunction "2_2") (pintype "passive"))
    )
    (net (code "32") (name "Net-(J11-PadTIP)") (class "Default")
      (node (ref "J11") (pin "TIP") (pinfunction "TIP_TIP") (pintype "passive"))
      (node (ref "R11") (pin "2") (pinfunction "2_2") (pintype "passive"))
    )
    (net (code "33") (name "Net-(J12-PadTIP)") (class "Default")
      (node (ref "J12") (pin "TIP") (pinfunction "TIP_TIP") (pintype "passive"))
      (node (ref "R12") (pin "2") (pinfunction "2_2") (pintype "passive"))
    )
    (net (code "34") (name "Net-(J13-PadTIP)") (class "Default")
      (node (ref "J13") (pin "TIP") (pinfunction "TIP_TIP") (pintype "passive"))
      (node (ref "R13") (pin "2") (pinfunction "2_2") (pintype "passive"))
    )
    (net (code "35") (name "Net-(J14-PadTIP)") (class "Default")
      (node (ref "J14") (pin "TIP") (pinfunction "TIP_TIP") (pintype "passive"))
      (node (ref "R14") (pin "2") (pinfunction "2_2") (pintype "passive"))
    )
    (net (code "36") (name "Net-(J15-PadTIP)") (class "Default")
      (node (ref "J15") (pin "TIP") (pinfunction "TIP_TIP") (pintype "passive"))
      (node (ref "R15") (pin "2") (pinfunction "2_2") (pintype "passive"))
    )
    (net (code "37") (name "Net-(J16-PadTIP)") (class "Default")
      (node (ref "J16") (pin "TIP") (pinfunction "TIP_TIP") (pintype "passive"))
      (node (ref "R16") (pin "2") (pinfunction "2_2") (pintype "passive"))
    )
    (net (code "38") (name "Net-(JP1-LEFT)") (class "Default")
      (node (ref "JP1") (pin "TIP") (pinfunction "LEFT_TIP") (pintype "bidirectional"))
      (node (ref "S1") (pin "P2") (pinfunction "5_P2") (pintype "bidirectional"))
    )
    (net (code "39") (name "Net-(JP1-RIGHT)") (class "Default")
      (node (ref "JP1") (pin "RING") (pinfunction "RIGHT_RING") (pintype "bidirectional"))
      (node (ref "S1") (pin "P1") (pinfunction "2_P1") (pintype "bidirectional"))
    )
    (net (code "40") (name "Net-(S1-1)") (class "Default")
      (node (ref "R52") (pin "1") (pinfunction "1_1") (pintype "passive"))
      (node (ref "S1") (pin "P1-TA") (pinfunction "1_P1-TA") (pintype "bidirectional"))
      (node (ref "S1") (pin "P2-TB") (pinfunction "6_P2-TB") (pintype "bidirectional"))
    )
    (net (code "41") (name "Net-(S1-3)") (class "Default")
      (node (ref "R49") (pin "1") (pinfunction "1_1") (pintype "passive"))
      (node (ref "S1") (pin "P1-TB") (pinfunction "3_P1-TB") (pintype "bidirectional"))
      (node (ref "S1") (pin "P2-TA") (pinfunction "4_P2-TA") (pintype "bidirectional"))
    )
    (net (code "42") (name "Net-(U2A-+IN)") (class "Default")
      (node (ref "R35") (pin "1") (pinfunction "1_1") (pintype "passive"))
      (node (ref "U$1") (pin "2") (pinfunction "2_2") (pintype "bidirectional"))
      (node (ref "U2") (pin "3") (pinfunction "+IN_3") (pintype "input"))
    )
    (net (code "43") (name "Net-(U2A--IN)") (class "Default")
      (node (ref "R1") (pin "1") (pinfunction "1_1") (pintype "passive"))
      (node (ref "U2") (pin "1") (pinfunction "OUT_1") (pintype "output"))
      (node (ref "U2") (pin "2") (pinfunction "-IN_2") (pintype "input"))
    )
    (net (code "44") (name "Net-(U2B-+IN)") (class "Default")
      (node (ref "R35") (pin "2") (pinfunction "2_2") (pintype "passive"))
      (node (ref "R36") (pin "2") (pinfunction "2_2") (pintype "passive"))
      (node (ref "U2") (pin "5") (pinfunction "+IN_5") (pintype "input"))
    )
    (net (code "45") (name "Net-(U2C-+IN)") (class "Default")
      (node (ref "R21") (pin "2") (pinfunction "2_2") (pintype "passive"))
      (node (ref "R22") (pin "2") (pinfunction "2_2") (pintype "passive"))
      (node (ref "U2") (pin "10") (pinfunction "+IN_10") (pintype "input"))
    )
    (net (code "46") (name "Net-(U2D-+IN)") (class "Default")
      (node (ref "R21") (pin "1") (pinfunction "1_1") (pintype "passive"))
      (node (ref "U$2") (pin "2") (pinfunction "2_2") (pintype "bidirectional"))
      (node (ref "U2") (pin "12") (pinfunction "+IN_12") (pintype "input"))
    )
    (net (code "47") (name "Net-(U2D--IN)") (class "Default")
      (node (ref "R2") (pin "1") (pinfunction "1_1") (pintype "passive"))
      (node (ref "U2") (pin "13") (pinfunction "-IN_13") (pintype "input"))
      (node (ref "U2") (pin "14") (pinfunction "OUT_14") (pintype "output"))
    )
    (net (code "48") (name "Net-(U3A-+IN)") (class "Default")
      (node (ref "R37") (pin "1") (pinfunction "1_1") (pintype "passive"))
      (node (ref "U$3") (pin "2") (pinfunction "2_2") (pintype "bidirectional"))
      (node (ref "U3") (pin "3") (pinfunction "+IN_3") (pintype "input"))
    )
    (net (code "49") (name "Net-(U3A--IN)") (class "Default")
      (node (ref "R3") (pin "1") (pinfunction "1_1") (pintype "passive"))
      (node (ref "U3") (pin "1") (pinfunction "OUT_1") (pintype "output"))
      (node (ref "U3") (pin "2") (pinfunction "-IN_2") (pintype "input"))
    )
    (net (code "50") (name "Net-(U3B-+IN)") (class "Default")
      (node (ref "R37") (pin "2") (pinfunction "2_2") (pintype "passive"))
      (node (ref "R38") (pin "2") (pinfunction "2_2") (pintype "passive"))
      (node (ref "U3") (pin "5") (pinfunction "+IN_5") (pintype "input"))
    )
    (net (code "51") (name "Net-(U3C-+IN)") (class "Default")
      (node (ref "R23") (pin "2") (pinfunction "2_2") (pintype "passive"))
      (node (ref "R24") (pin "2") (pinfunction "2_2") (pintype "passive"))
      (node (ref "U3") (pin "10") (pinfunction "+IN_10") (pintype "input"))
    )
    (net (code "52") (name "Net-(U3D-+IN)") (class "Default")
      (node (ref "R23") (pin "1") (pinfunction "1_1") (pintype "passive"))
      (node (ref "U$4") (pin "2") (pinfunction "2_2") (pintype "bidirectional"))
      (node (ref "U3") (pin "12") (pinfunction "+IN_12") (pintype "input"))
    )
    (net (code "53") (name "Net-(U3D--IN)") (class "Default")
      (node (ref "R4") (pin "1") (pinfunction "1_1") (pintype "passive"))
      (node (ref "U3") (pin "13") (pinfunction "-IN_13") (pintype "input"))
      (node (ref "U3") (pin "14") (pinfunction "OUT_14") (pintype "output"))
    )
    (net (code "54") (name "Net-(U4A-+IN)") (class "Default")
      (node (ref "R39") (pin "1") (pinfunction "1_1") (pintype "passive"))
      (node (ref "U$5") (pin "2") (pinfunction "2_2") (pintype "bidirectional"))
      (node (ref "U4") (pin "3") (pinfunction "+IN_3") (pintype "input"))
    )
    (net (code "55") (name "Net-(U4A--IN)") (class "Default")
      (node (ref "R5") (pin "1") (pinfunction "1_1") (pintype "passive"))
      (node (ref "U4") (pin "1") (pinfunction "OUT_1") (pintype "output"))
      (node (ref "U4") (pin "2") (pinfunction "-IN_2") (pintype "input"))
    )
    (net (code "56") (name "Net-(U4B-+IN)") (class "Default")
      (node (ref "R39") (pin "2") (pinfunction "2_2") (pintype "passive"))
      (node (ref "R40") (pin "2") (pinfunction "2_2") (pintype "passive"))
      (node (ref "U4") (pin "5") (pinfunction "+IN_5") (pintype "input"))
    )
    (net (code "57") (name "Net-(U4C-+IN)") (class "Default")
      (node (ref "R25") (pin "2") (pinfunction "2_2") (pintype "passive"))
      (node (ref "R26") (pin "2") (pinfunction "2_2") (pintype "passive"))
      (node (ref "U4") (pin "10") (pinfunction "+IN_10") (pintype "input"))
    )
    (net (code "58") (name "Net-(U4D-+IN)") (class "Default")
      (node (ref "R25") (pin "1") (pinfunction "1_1") (pintype "passive"))
      (node (ref "U$6") (pin "2") (pinfunction "2_2") (pintype "bidirectional"))
      (node (ref "U4") (pin "12") (pinfunction "+IN_12") (pintype "input"))
    )
    (net (code "59") (name "Net-(U4D--IN)") (class "Default")
      (node (ref "R6") (pin "1") (pinfunction "1_1") (pintype "passive"))
      (node (ref "U4") (pin "13") (pinfunction "-IN_13") (pintype "input"))
      (node (ref "U4") (pin "14") (pinfunction "OUT_14") (pintype "output"))
    )
    (net (code "60") (name "Net-(U5A-+IN)") (class "Default")
      (node (ref "R41") (pin "1") (pinfunction "1_1") (pintype "passive"))
      (node (ref "U$7") (pin "2") (pinfunction "2_2") (pintype "bidirectional"))
      (node (ref "U5") (pin "3") (pinfunction "+IN_3") (pintype "input"))
    )
    (net (code "61") (name "Net-(U5A--IN)") (class "Default")
      (node (ref "R7") (pin "1") (pinfunction "1_1") (pintype "passive"))
      (node (ref "U5") (pin "1") (pinfunction "OUT_1") (pintype "output"))
      (node (ref "U5") (pin "2") (pinfunction "-IN_2") (pintype "input"))
    )
    (net (code "62") (name "Net-(U5B-+IN)") (class "Default")
      (node (ref "R41") (pin "2") (pinfunction "2_2") (pintype "passive"))
      (node (ref "R42") (pin "2") (pinfunction "2_2") (pintype "passive"))
      (node (ref "U5") (pin "5") (pinfunction "+IN_5") (pintype "input"))
    )
    (net (code "63") (name "Net-(U5C-+IN)") (class "Default")
      (node (ref "R27") (pin "2") (pinfunction "2_2") (pintype "passive"))
      (node (ref "R28") (pin "2") (pinfunction "2_2") (pintype "passive"))
      (node (ref "U5") (pin "10") (pinfunction "+IN_10") (pintype "input"))
    )
    (net (code "64") (name "Net-(U5D-+IN)") (class "Default")
      (node (ref "R27") (pin "1") (pinfunction "1_1") (pintype "passive"))
      (node (ref "U$8") (pin "2") (pinfunction "2_2") (pintype "bidirectional"))
      (node (ref "U5") (pin "12") (pinfunction "+IN_12") (pintype "input"))
    )
    (net (code "65") (name "Net-(U5D--IN)") (class "Default")
      (node (ref "R8") (pin "1") (pinfunction "1_1") (pintype "passive"))
      (node (ref "U5") (pin "13") (pinfunction "-IN_13") (pintype "input"))
      (node (ref "U5") (pin "14") (pinfunction "OUT_14") (pintype "output"))
    )
    (net (code "66") (name "Net-(U6A-+IN)") (class "Default")
      (node (ref "R43") (pin "1") (pinfunction "1_1") (pintype "passive"))
      (node (ref "U$9") (pin "2") (pinfunction "2_2") (pintype "bidirectional"))
      (node (ref "U6") (pin "3") (pinfunction "+IN_3") (pintype "input"))
    )
    (net (code "67") (name "Net-(U6A--IN)") (class "Default")
      (node (ref "R9") (pin "1") (pinfunction "1_1") (pintype "passive"))
      (node (ref "U6") (pin "1") (pinfunction "OUT_1") (pintype "output"))
      (node (ref "U6") (pin "2") (pinfunction "-IN_2") (pintype "input"))
    )
    (net (code "68") (name "Net-(U6B-+IN)") (class "Default")
      (node (ref "R43") (pin "2") (pinfunction "2_2") (pintype "passive"))
      (node (ref "R44") (pin "2") (pinfunction "2_2") (pintype "passive"))
      (node (ref "U6") (pin "5") (pinfunction "+IN_5") (pintype "input"))
    )
    (net (code "69") (name "Net-(U6C-+IN)") (class "Default")
      (node (ref "R29") (pin "2") (pinfunction "2_2") (pintype "passive"))
      (node (ref "R30") (pin "2") (pinfunction "2_2") (pintype "passive"))
      (node (ref "U6") (pin "10") (pinfunction "+IN_10") (pintype "input"))
    )
    (net (code "70") (name "Net-(U6D-+IN)") (class "Default")
      (node (ref "R29") (pin "1") (pinfunction "1_1") (pintype "passive"))
      (node (ref "U$10") (pin "2") (pinfunction "2_2") (pintype "bidirectional"))
      (node (ref "U6") (pin "12") (pinfunction "+IN_12") (pintype "input"))
    )
    (net (code "71") (name "Net-(U6D--IN)") (class "Default")
      (node (ref "R10") (pin "1") (pinfunction "1_1") (pintype "passive"))
      (node (ref "U6") (pin "13") (pinfunction "-IN_13") (pintype "input"))
      (node (ref "U6") (pin "14") (pinfunction "OUT_14") (pintype "output"))
    )
    (net (code "72") (name "Net-(U7A-+IN)") (class "Default")
      (node (ref "R45") (pin "1") (pinfunction "1_1") (pintype "passive"))
      (node (ref "U$11") (pin "2") (pinfunction "2_2") (pintype "bidirectional"))
      (node (ref "U7") (pin "3") (pinfunction "+IN_3") (pintype "input"))
    )
    (net (code "73") (name "Net-(U7A--IN)") (class "Default")
      (node (ref "R11") (pin "1") (pinfunction "1_1") (pintype "passive"))
      (node (ref "U7") (pin "1") (pinfunction "OUT_1") (pintype "output"))
      (node (ref "U7") (pin "2") (pinfunction "-IN_2") (pintype "input"))
    )
    (net (code "74") (name "Net-(U7B-+IN)") (class "Default")
      (node (ref "R45") (pin "2") (pinfunction "2_2") (pintype "passive"))
      (node (ref "R46") (pin "2") (pinfunction "2_2") (pintype "passive"))
      (node (ref "U7") (pin "5") (pinfunction "+IN_5") (pintype "input"))
    )
    (net (code "75") (name "Net-(U7C-+IN)") (class "Default")
      (node (ref "R31") (pin "2") (pinfunction "2_2") (pintype "passive"))
      (node (ref "R32") (pin "2") (pinfunction "2_2") (pintype "passive"))
      (node (ref "U7") (pin "10") (pinfunction "+IN_10") (pintype "input"))
    )
    (net (code "76") (name "Net-(U7D-+IN)") (class "Default")
      (node (ref "R31") (pin "1") (pinfunction "1_1") (pintype "passive"))
      (node (ref "U$12") (pin "2") (pinfunction "2_2") (pintype "bidirectional"))
      (node (ref "U7") (pin "12") (pinfunction "+IN_12") (pintype "input"))
    )
    (net (code "77") (name "Net-(U7D--IN)") (class "Default")
      (node (ref "R12") (pin "1") (pinfunction "1_1") (pintype "passive"))
      (node (ref "U7") (pin "13") (pinfunction "-IN_13") (pintype "input"))
      (node (ref "U7") (pin "14") (pinfunction "OUT_14") (pintype "output"))
    )
    (net (code "78") (name "Net-(U8A-+IN)") (class "Default")
      (node (ref "R47") (pin "1") (pinfunction "1_1") (pintype "passive"))
      (node (ref "U$13") (pin "2") (pinfunction "2_2") (pintype "bidirectional"))
      (node (ref "U8") (pin "3") (pinfunction "+IN_3") (pintype "input"))
    )
    (net (code "79") (name "Net-(U8A--IN)") (class "Default")
      (node (ref "R13") (pin "1") (pinfunction "1_1") (pintype "passive"))
      (node (ref "U8") (pin "1") (pinfunction "OUT_1") (pintype "output"))
      (node (ref "U8") (pin "2") (pinfunction "-IN_2") (pintype "input"))
    )
    (net (code "80") (name "Net-(U8B-+IN)") (class "Default")
      (node (ref "R47") (pin "2") (pinfunction "2_2") (pintype "passive"))
      (node (ref "R48") (pin "2") (pinfunction "2_2") (pintype "passive"))
      (node (ref "U8") (pin "5") (pinfunction "+IN_5") (pintype "input"))
    )
    (net (code "81") (name "Net-(U8C-+IN)") (class "Default")
      (node (ref "R33") (pin "2") (pinfunction "2_2") (pintype "passive"))
      (node (ref "R34") (pin "2") (pinfunction "2_2") (pintype "passive"))
      (node (ref "U8") (pin "10") (pinfunction "+IN_10") (pintype "input"))
    )
    (net (code "82") (name "Net-(U8D-+IN)") (class "Default")
      (node (ref "R33") (pin "1") (pinfunction "1_1") (pintype "passive"))
      (node (ref "U$14") (pin "2") (pinfunction "2_2") (pintype "bidirectional"))
      (node (ref "U8") (pin "12") (pinfunction "+IN_12") (pintype "input"))
    )
    (net (code "83") (name "Net-(U8D--IN)") (class "Default")
      (node (ref "R14") (pin "1") (pinfunction "1_1") (pintype "passive"))
      (node (ref "U8") (pin "13") (pinfunction "-IN_13") (pintype "input"))
      (node (ref "U8") (pin "14") (pinfunction "OUT_14") (pintype "output"))
    )
    (net (code "84") (name "Net-(U9A-+IN)") (class "Default")
      (node (ref "R50") (pin "1") (pinfunction "1_1") (pintype "passive"))
      (node (ref "U$15") (pin "2") (pinfunction "2_2") (pintype "bidirectional"))
      (node (ref "U9") (pin "3") (pinfunction "+IN_3") (pintype "input"))
    )
    (net (code "85") (name "Net-(U9A--IN)") (class "Default")
      (node (ref "R15") (pin "1") (pinfunction "1_1") (pintype "passive"))
      (node (ref "U9") (pin "1") (pinfunction "OUT_1") (pintype "output"))
      (node (ref "U9") (pin "2") (pinfunction "-IN_2") (pintype "input"))
    )
    (net (code "86") (name "Net-(U9B-+IN)") (class "Default")
      (node (ref "R50") (pin "2") (pinfunction "2_2") (pintype "passive"))
      (node (ref "R51") (pin "2") (pinfunction "2_2") (pintype "passive"))
      (node (ref "U9") (pin "5") (pinfunction "+IN_5") (pintype "input"))
    )
    (net (code "87") (name "Net-(U9C-+IN)") (class "Default")
      (node (ref "R19") (pin "2") (pinfunction "2_2") (pintype "passive"))
      (node (ref "R20") (pin "2") (pinfunction "2_2") (pintype "passive"))
      (node (ref "U9") (pin "10") (pinfunction "+IN_10") (pintype "input"))
    )
    (net (code "88") (name "Net-(U9D-+IN)") (class "Default")
      (node (ref "R19") (pin "1") (pinfunction "1_1") (pintype "passive"))
      (node (ref "U$16") (pin "2") (pinfunction "2_2") (pintype "bidirectional"))
      (node (ref "U9") (pin "12") (pinfunction "+IN_12") (pintype "input"))
    )
    (net (code "89") (name "Net-(U9D--IN)") (class "Default")
      (node (ref "R16") (pin "1") (pinfunction "1_1") (pintype "passive"))
      (node (ref "U9") (pin "13") (pinfunction "-IN_13") (pintype "input"))
      (node (ref "U9") (pin "14") (pinfunction "OUT_14") (pintype "output"))
    )
    (net (code "90") (name "S0") (class "Default")
      (node (ref "U$17") (pin "8") (pinfunction "8/TX3_8") (pintype "bidirectional"))
      (node (ref "U1") (pin "10") (pinfunction "S0_10") (pintype "input"))
    )
    (net (code "91") (name "S1") (class "Default")
      (node (ref "U$17") (pin "7") (pinfunction "7/RX3_7") (pintype "bidirectional"))
      (node (ref "U1") (pin "11") (pinfunction "S1_11") (pintype "input"))
    )
    (net (code "92") (name "S2") (class "Default")
      (node (ref "U$17") (pin "6") (pinfunction "6/PWM_6") (pintype "bidirectional"))
      (node (ref "U1") (pin "14") (pinfunction "S2_14") (pintype "input"))
    )
    (net (code "93") (name "S3") (class "Default")
      (node (ref "U$17") (pin "5") (pinfunction "5/PWM_5") (pintype "bidirectional"))
      (node (ref "U1") (pin "13") (pinfunction "S3_13") (pintype "input"))
    )
    (net (code "94") (name "SCL") (class "Default")
      (node (ref "D1") (pin "A") (pinfunction "A_A") (pintype "passive"))
      (node (ref "D2") (pin "C") (pinfunction "C_C") (pintype "passive"))
      (node (ref "JP2") (pin "RING") (pinfunction "RIGHT_RING") (pintype "bidirectional"))
      (node (ref "R17") (pin "1") (pinfunction "1_1") (pintype "passive"))
      (node (ref "U$17") (pin "19/A5") (pinfunction "19/A5/T/SCL0_19/A5") (pintype "bidirectional"))
    )
    (net (code "95") (name "SDA") (class "Default")
      (node (ref "D3") (pin "C") (pinfunction "C_C") (pintype "passive"))
      (node (ref "D4") (pin "A") (pinfunction "A_A") (pintype "passive"))
      (node (ref "JP2") (pin "TIP") (pinfunction "LEFT_TIP") (pintype "bidirectional"))
      (node (ref "R18") (pin "1") (pinfunction "1_1") (pintype "passive"))
      (node (ref "U$17") (pin "18/A4") (pinfunction "18/A4/T/SDA0_18/A4") (pintype "bidirectional"))
    )
    (net (code "96") (name "unconnected-(J1-SWITCH-PadSW)") (class "Default")
      (node (ref "J1") (pin "SW") (pinfunction "SWITCH_SW") (pintype "passive"))
    )
    (net (code "97") (name "unconnected-(J2-SWITCH-PadSW)") (class "Default")
      (node (ref "J2") (pin "SW") (pinfunction "SWITCH_SW") (pintype "passive"))
    )
    (net (code "98") (name "unconnected-(J3-SWITCH-PadSW)") (class "Default")
      (node (ref "J3") (pin "SW") (pinfunction "SWITCH_SW") (pintype "passive"))
    )
    (net (code "99") (name "unconnected-(J4-SWITCH-PadSW)") (class "Default")
      (node (ref "J4") (pin "SW") (pinfunction "SWITCH_SW") (pintype "passive"))
    )
    (net (code "100") (name "unconnected-(J5-SWITCH-PadSW)") (class "Default")
      (node (ref "J5") (pin "SW") (pinfunction "SWITCH_SW") (pintype "passive"))
    )
    (net (code "101") (name "unconnected-(J6-SWITCH-PadSW)") (class "Default")
      (node (ref "J6") (pin "SW") (pinfunction "SWITCH_SW") (pintype "passive"))
    )
    (net (code "102") (name "unconnected-(J7-SWITCH-PadSW)") (class "Default")
      (node (ref "J7") (pin "SW") (pinfunction "SWITCH_SW") (pintype "passive"))
    )
    (net (code "103") (name "unconnected-(J8-SWITCH-PadSW)") (class "Default")
      (node (ref "J8") (pin "SW") (pinfunction "SWITCH_SW") (pintype "passive"))
    )
    (net (code "104") (name "unconnected-(J9-SWITCH-PadSW)") (class "Default")
      (node (ref "J9") (pin "SW") (pinfunction "SWITCH_SW") (pintype "passive"))
    )
    (net (code "105") (name "unconnected-(J10-SWITCH-PadSW)") (class "Default")
      (node (ref "J10") (pin "SW") (pinfunction "SWITCH_SW") (pintype "passive"))
    )
    (net (code "106") (name "unconnected-(J11-SWITCH-PadSW)") (class "Default")
      (node (ref "J11") (pin "SW") (pinfunction "SWITCH_SW") (pintype "passive"))
    )
    (net (code "107") (name "unconnected-(J12-SWITCH-PadSW)") (class "Default")
      (node (ref "J12") (pin "SW") (pinfunction "SWITCH_SW") (pintype "passive"))
    )
    (net (code "108") (name "unconnected-(J13-SWITCH-PadSW)") (class "Default")
      (node (ref "J13") (pin "SW") (pinfunction "SWITCH_SW") (pintype "passive"))
    )
    (net (code "109") (name "unconnected-(J14-SWITCH-PadSW)") (class "Default")
      (node (ref "J14") (pin "SW") (pinfunction "SWITCH_SW") (pintype "passive"))
    )
    (net (code "110") (name "unconnected-(J15-SWITCH-PadSW)") (class "Default")
      (node (ref "J15") (pin "SW") (pinfunction "SWITCH_SW") (pintype "passive"))
    )
    (net (code "111") (name "unconnected-(J16-SWITCH-PadSW)") (class "Default")
      (node (ref "J16") (pin "SW") (pinfunction "SWITCH_SW") (pintype "passive"))
    )
    (net (code "112") (name "unconnected-(U$17-0{slash}RX1{slash}T-Pad0)") (class "Default")
      (node (ref "U$17") (pin "0") (pinfunction "0/RX1/T_0") (pintype "bidirectional"))
    )
    (net (code "113") (name "unconnected-(U$17-3{slash}CAN-TX{slash}PWM-Pad3)") (class "Default")
      (node (ref "U$17") (pin "3") (pinfunction "3/CAN-TX/PWM_3") (pintype "bidirectional"))
    )
    (net (code "114") (name "unconnected-(U$17-4{slash}CAN-RX{slash}PWM-Pad4)") (class "Default")
      (node (ref "U$17") (pin "4") (pinfunction "4/CAN-RX/PWM_4") (pintype "bidirectional"))
    )
    (net (code "115") (name "unconnected-(U$17-9{slash}RX2{slash}PWM-Pad9)") (class "Default")
      (node (ref "U$17") (pin "9") (pinfunction "9/RX2/PWM_9") (pintype "bidirectional"))
    )
    (net (code "116") (name "unconnected-(U$17-10{slash}TX2{slash}PWM-Pad10)") (class "Default")
      (node (ref "U$17") (pin "10") (pinfunction "10/TX2/PWM_10") (pintype "bidirectional"))
    )
    (net (code "117") (name "unconnected-(U$17-11{slash}MOSI-Pad11)") (class "Default")
      (node (ref "U$17") (pin "11") (pinfunction "11/MOSI_11") (pintype "bidirectional"))
    )
    (net (code "118") (name "unconnected-(U$17-12{slash}MISO-Pad12)") (class "Default")
      (node (ref "U$17") (pin "12") (pinfunction "12/MISO_12") (pintype "bidirectional"))
    )
    (net (code "119") (name "unconnected-(U$17-13{slash}SCK{slash}LED-Pad13)") (class "Default")
      (node (ref "U$17") (pin "13") (pinfunction "13/SCK/LED_13") (pintype "bidirectional"))
    )
    (net (code "120") (name "unconnected-(U$17-15{slash}A1{slash}T-Pad15{slash}A1)") (class "Default")
      (node (ref "U$17") (pin "15/A1") (pinfunction "15/A1/T_15/A1") (pintype "bidirectional"))
    )
    (net (code "121") (name "unconnected-(U$17-16{slash}A2{slash}T-Pad16{slash}A2)") (class "Default")
      (node (ref "U$17") (pin "16/A2") (pinfunction "16/A2/T_16/A2") (pintype "bidirectional"))
    )
    (net (code "122") (name "unconnected-(U$17-17{slash}A3{slash}T-Pad17{slash}A3)") (class "Default")
      (node (ref "U$17") (pin "17/A3") (pinfunction "17/A3/T_17/A3") (pintype "bidirectional"))
    )
    (net (code "123") (name "unconnected-(U$17-20{slash}A6{slash}PWM-Pad20{slash}A6)") (class "Default")
      (node (ref "U$17") (pin "20/A6") (pinfunction "20/A6/PWM_20/A6") (pintype "bidirectional"))
    )
    (net (code "124") (name "unconnected-(U$17-21{slash}A7{slash}PWM-Pad21{slash}A7)") (class "Default")
      (node (ref "U$17") (pin "21/A7") (pinfunction "21/A7/PWM_21/A7") (pintype "bidirectional"))
    )
    (net (code "125") (name "unconnected-(U$17-22{slash}A8{slash}T{slash}PWM-Pad22{slash}A8)") (class "Default")
      (node (ref "U$17") (pin "22/A8") (pinfunction "22/A8/T/PWM_22/A8") (pintype "bidirectional"))
    )
    (net (code "126") (name "unconnected-(U$17-23{slash}A9{slash}T{slash}PWM-Pad23{slash}A9)") (class "Default")
      (node (ref "U$17") (pin "23/A9") (pinfunction "23/A9/T/PWM_23/A9") (pintype "bidirectional"))
    )
    (net (code "127") (name "unconnected-(U$17-Pad2)") (class "Default")
      (node (ref "U$17") (pin "2") (pinfunction "2_2") (pintype "bidirectional"))
    )
  )
)
